# Kasli-SOC_linear.net
KiCad netlist of a schematic drawn in Altium Designer
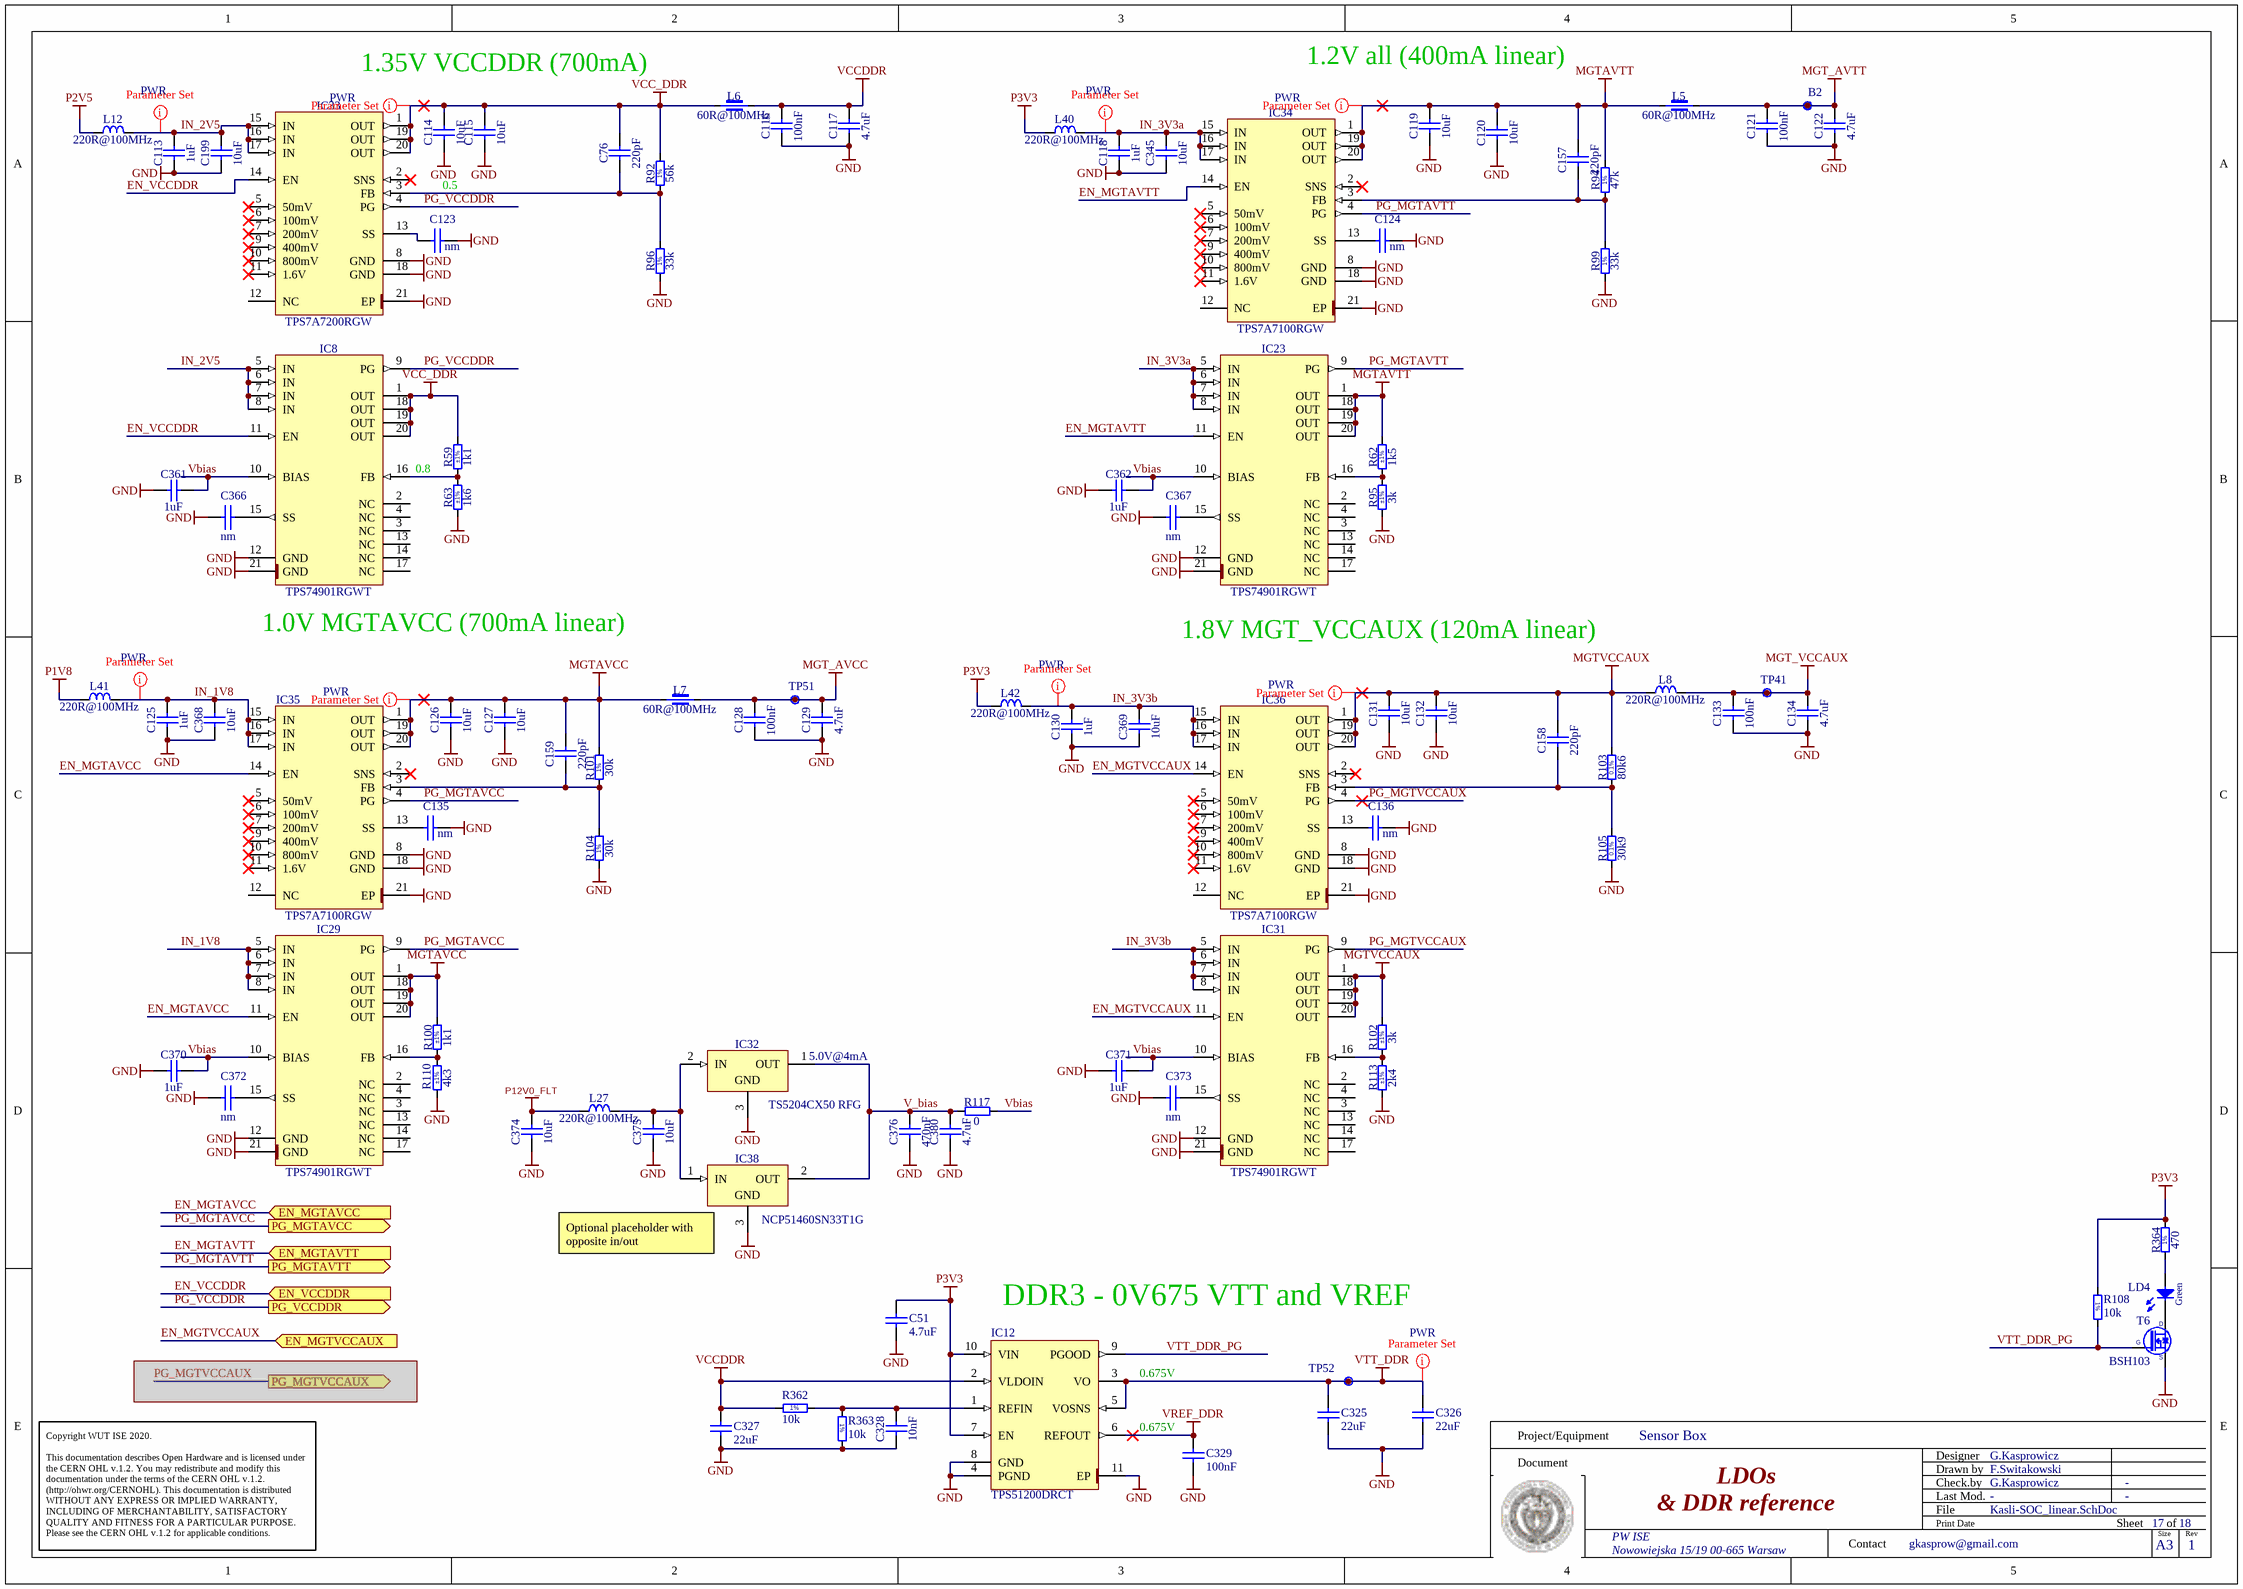
[diagram p0: Kasli-SOC_linear.SchDoc]

(export (version "E")
  (design (tool "Eeschema 10.0.6"))
  (components
    (comp (ref "B2")
      (value "SMD Pad")
      (footprint "C75")
      (description "Through Hole Pad")
      (fields (field (name "PART NUMBER") "SMD_PAD_D0.75MM") (field (name "AUTHOR") "CERN DEM BC"))
      (libsource (lib "Eletro-mechanical") (part "Single SMD Pad (Round)"))
    )
    (comp (ref "C51")
      (value "4.7uF")
      (footprint "CAPC1608X87N")
      (description "Non-polarised capacitor")
      (fields
        (field (name "PART NUMBER") "CC0603_4.7UF_6.3V_10%_X5R")
        (field (name "VOLTAGE") "6.3V")
        (field (name "AUTHOR") "CERN DEM JLC")
      )
      (libsource (lib "Capacitors") (part "Capacitor - non polarized"))
    )
    (comp (ref "C76")
      (value "220pF")
      (footprint "CAPC1005X55N")
      (description "Non-polarised capacitor")
      (fields
        (field (name "PART NUMBER") "CC0402_220PF_50V_5%_C0G")
        (field (name "VOLTAGE") "50V")
        (field (name "AUTHOR") "CERN DEM JLC")
      )
      (libsource (lib "Capacitors") (part "Capacitor - non polarized"))
    )
    (comp (ref "C113")
      (value "1uF")
      (footprint "CAPC1608X87N")
      (description "Non-polarised capacitor")
      (fields
        (field (name "PART NUMBER") "CC0603_1UF_25V_10%_X7R")
        (field (name "VOLTAGE") "25V")
        (field (name "AUTHOR") "CERN DEM JLC")
      )
      (libsource (lib "Capacitors") (part "Capacitor - non polarized"))
    )
    (comp (ref "C114")
      (value "10uF")
      (footprint "CAPC1005X70N")
      (description "Non-polarised capacitor")
      (fields
        (field (name "PART NUMBER") "CC0402_10UF_6.3V_20%_X5R")
        (field (name "VOLTAGE") "6.3V")
        (field (name "AUTHOR") "CERN DEM JLC")
      )
      (libsource (lib "Capacitors") (part "Capacitor - non polarized"))
    )
    (comp (ref "C115")
      (value "10uF")
      (footprint "CAPC1005X70N")
      (description "Non-polarised capacitor")
      (fields
        (field (name "PART NUMBER") "CC0402_10UF_6.3V_20%_X5R")
        (field (name "VOLTAGE") "6.3V")
        (field (name "AUTHOR") "CERN DEM JLC")
      )
      (libsource (lib "Capacitors") (part "Capacitor - non polarized"))
    )
    (comp (ref "C116")
      (value "100nF")
      (footprint "CAPC1005X55N")
      (description "Non-polarised capacitor")
      (fields
        (field (name "PART NUMBER") "CC0402_100NF_16V_10%_X7R")
        (field (name "VOLTAGE") "16V")
        (field (name "AUTHOR") "CERN DEM JLC")
      )
      (libsource (lib "Capacitors") (part "Capacitor - non polarized"))
    )
    (comp (ref "C117")
      (value "4.7uF")
      (footprint "CAPC1005X55N")
      (description "Non-polarised capacitor")
      (fields
        (field (name "PART NUMBER") "CC0402_4.7UF_6.3V_20%_X5R")
        (field (name "VOLTAGE") "6.3V")
        (field (name "AUTHOR") "CERN DEM JLC")
      )
      (libsource (lib "Capacitors") (part "Capacitor - non polarized"))
    )
    (comp (ref "C118")
      (value "1uF")
      (footprint "CAPC1608X87N")
      (description "Non-polarised capacitor")
      (fields
        (field (name "PART NUMBER") "CC0603_1UF_25V_10%_X7R")
        (field (name "VOLTAGE") "25V")
        (field (name "AUTHOR") "CERN DEM JLC")
      )
      (libsource (lib "Capacitors") (part "Capacitor - non polarized"))
    )
    (comp (ref "C119")
      (value "10uF")
      (footprint "CAPC1005X70N")
      (description "Non-polarised capacitor")
      (fields
        (field (name "PART NUMBER") "CC0402_10UF_6.3V_20%_X5R")
        (field (name "VOLTAGE") "6.3V")
        (field (name "AUTHOR") "CERN DEM JLC")
      )
      (libsource (lib "Capacitors") (part "Capacitor - non polarized"))
    )
    (comp (ref "C120")
      (value "10uF")
      (footprint "CAPC1005X70N")
      (description "Non-polarised capacitor")
      (fields
        (field (name "PART NUMBER") "CC0402_10UF_6.3V_20%_X5R")
        (field (name "VOLTAGE") "6.3V")
        (field (name "AUTHOR") "CERN DEM JLC")
      )
      (libsource (lib "Capacitors") (part "Capacitor - non polarized"))
    )
    (comp (ref "C121")
      (value "100nF")
      (footprint "CAPC1005X55N")
      (description "Non-polarised capacitor")
      (fields
        (field (name "PART NUMBER") "CC0402_100NF_16V_10%_X7R")
        (field (name "VOLTAGE") "16V")
        (field (name "AUTHOR") "CERN DEM JLC")
      )
      (libsource (lib "Capacitors") (part "Capacitor - non polarized"))
    )
    (comp (ref "C122")
      (value "4.7uF")
      (footprint "CAPC1005X55N")
      (description "Non-polarised capacitor")
      (fields
        (field (name "PART NUMBER") "CC0402_4.7UF_6.3V_20%_X5R")
        (field (name "VOLTAGE") "6.3V")
        (field (name "AUTHOR") "CERN DEM JLC")
      )
      (libsource (lib "Capacitors") (part "Capacitor - non polarized"))
    )
    (comp (ref "C123")
      (value "nm")
      (footprint "0402C")
      (description "Capacitor SMD")
      (libsource (lib "LIBRARY_SCH") (part "CAP_SMD_0402"))
    )
    (comp (ref "C124")
      (value "nm")
      (footprint "0402C")
      (description "Capacitor SMD")
      (libsource (lib "LIBRARY_SCH") (part "CAP_SMD_0402"))
    )
    (comp (ref "C125")
      (value "1uF")
      (footprint "CAPC1608X87N")
      (description "Non-polarised capacitor")
      (fields
        (field (name "PART NUMBER") "CC0603_1UF_25V_10%_X7R")
        (field (name "VOLTAGE") "25V")
        (field (name "AUTHOR") "CERN DEM JLC")
      )
      (libsource (lib "Capacitors") (part "Capacitor - non polarized"))
    )
    (comp (ref "C126")
      (value "10uF")
      (footprint "CAPC1005X70N")
      (description "Non-polarised capacitor")
      (fields
        (field (name "PART NUMBER") "CC0402_10UF_6.3V_20%_X5R")
        (field (name "VOLTAGE") "6.3V")
        (field (name "AUTHOR") "CERN DEM JLC")
      )
      (libsource (lib "Capacitors") (part "Capacitor - non polarized"))
    )
    (comp (ref "C127")
      (value "10uF")
      (footprint "CAPC1005X70N")
      (description "Non-polarised capacitor")
      (fields
        (field (name "PART NUMBER") "CC0402_10UF_6.3V_20%_X5R")
        (field (name "VOLTAGE") "6.3V")
        (field (name "AUTHOR") "CERN DEM JLC")
      )
      (libsource (lib "Capacitors") (part "Capacitor - non polarized"))
    )
    (comp (ref "C128")
      (value "100nF")
      (footprint "CAPC1005X55N")
      (description "Non-polarised capacitor")
      (fields
        (field (name "PART NUMBER") "CC0402_100NF_16V_10%_X7R")
        (field (name "VOLTAGE") "16V")
        (field (name "AUTHOR") "CERN DEM JLC")
      )
      (libsource (lib "Capacitors") (part "Capacitor - non polarized"))
    )
    (comp (ref "C129")
      (value "4.7uF")
      (footprint "CAPC1005X55N")
      (description "Non-polarised capacitor")
      (fields
        (field (name "PART NUMBER") "CC0402_4.7UF_6.3V_20%_X5R")
        (field (name "VOLTAGE") "6.3V")
        (field (name "AUTHOR") "CERN DEM JLC")
      )
      (libsource (lib "Capacitors") (part "Capacitor - non polarized"))
    )
    (comp (ref "C130")
      (value "1uF")
      (footprint "CAPC1608X87N")
      (description "Non-polarised capacitor")
      (fields
        (field (name "PART NUMBER") "CC0603_1UF_25V_10%_X7R")
        (field (name "VOLTAGE") "25V")
        (field (name "AUTHOR") "CERN DEM JLC")
      )
      (libsource (lib "Capacitors") (part "Capacitor - non polarized"))
    )
    (comp (ref "C131")
      (value "10uF")
      (footprint "CAPC1005X70N")
      (description "Non-polarised capacitor")
      (fields
        (field (name "PART NUMBER") "CC0402_10UF_6.3V_20%_X5R")
        (field (name "VOLTAGE") "6.3V")
        (field (name "AUTHOR") "CERN DEM JLC")
      )
      (libsource (lib "Capacitors") (part "Capacitor - non polarized"))
    )
    (comp (ref "C132")
      (value "10uF")
      (footprint "CAPC1005X70N")
      (description "Non-polarised capacitor")
      (fields
        (field (name "PART NUMBER") "CC0402_10UF_6.3V_20%_X5R")
        (field (name "VOLTAGE") "6.3V")
        (field (name "AUTHOR") "CERN DEM JLC")
      )
      (libsource (lib "Capacitors") (part "Capacitor - non polarized"))
    )
    (comp (ref "C133")
      (value "100nF")
      (footprint "CAPC1005X55N")
      (description "Non-polarised capacitor")
      (fields
        (field (name "PART NUMBER") "CC0402_100NF_16V_10%_X7R")
        (field (name "VOLTAGE") "16V")
        (field (name "AUTHOR") "CERN DEM JLC")
      )
      (libsource (lib "Capacitors") (part "Capacitor - non polarized"))
    )
    (comp (ref "C134")
      (value "4.7uF")
      (footprint "CAPC1005X55N")
      (description "Non-polarised capacitor")
      (fields
        (field (name "PART NUMBER") "CC0402_4.7UF_6.3V_20%_X5R")
        (field (name "VOLTAGE") "6.3V")
        (field (name "AUTHOR") "CERN DEM JLC")
      )
      (libsource (lib "Capacitors") (part "Capacitor - non polarized"))
    )
    (comp (ref "C135")
      (value "nm")
      (footprint "0402C")
      (description "Capacitor SMD")
      (libsource (lib "LIBRARY_SCH") (part "CAP_SMD_0402"))
    )
    (comp (ref "C136")
      (value "nm")
      (footprint "0402C")
      (description "Capacitor SMD")
      (libsource (lib "LIBRARY_SCH") (part "CAP_SMD_0402"))
    )
    (comp (ref "C157")
      (value "220pF")
      (footprint "CAPC1005X55N")
      (description "Non-polarised capacitor")
      (fields
        (field (name "PART NUMBER") "CC0402_220PF_50V_5%_C0G")
        (field (name "VOLTAGE") "50V")
        (field (name "AUTHOR") "CERN DEM JLC")
      )
      (libsource (lib "Capacitors") (part "Capacitor - non polarized"))
    )
    (comp (ref "C158")
      (value "220pF")
      (footprint "CAPC1005X55N")
      (description "Non-polarised capacitor")
      (fields
        (field (name "PART NUMBER") "CC0402_220PF_50V_5%_C0G")
        (field (name "VOLTAGE") "50V")
        (field (name "AUTHOR") "CERN DEM JLC")
      )
      (libsource (lib "Capacitors") (part "Capacitor - non polarized"))
    )
    (comp (ref "C159")
      (value "220pF")
      (footprint "CAPC1005X55N")
      (description "Non-polarised capacitor")
      (fields
        (field (name "PART NUMBER") "CC0402_220PF_50V_5%_C0G")
        (field (name "VOLTAGE") "50V")
        (field (name "AUTHOR") "CERN DEM JLC")
      )
      (libsource (lib "Capacitors") (part "Capacitor - non polarized"))
    )
    (comp (ref "C199")
      (value "10uF")
      (footprint "CAPC1005X70N")
      (description "Non-polarised capacitor")
      (fields
        (field (name "PART NUMBER") "CC0402_10UF_6.3V_20%_X5R")
        (field (name "VOLTAGE") "6.3V")
        (field (name "AUTHOR") "CERN DEM JLC")
      )
      (libsource (lib "Capacitors") (part "Capacitor - non polarized"))
    )
    (comp (ref "C325")
      (value "22uF")
      (footprint "CAPC3216X180N")
      (description "Non-polarised capacitor")
      (fields
        (field (name "PART NUMBER") "CC1206_22UF_10V_10%_X7R")
        (field (name "VOLTAGE") "10V")
        (field (name "AUTHOR") "CERN DEM JLC")
      )
      (libsource (lib "Capacitors") (part "Capacitor - non polarized"))
    )
    (comp (ref "C326")
      (value "22uF")
      (footprint "CAPC3216X180N")
      (description "Non-polarised capacitor")
      (fields
        (field (name "PART NUMBER") "CC1206_22UF_10V_10%_X7R")
        (field (name "VOLTAGE") "10V")
        (field (name "AUTHOR") "CERN DEM JLC")
      )
      (libsource (lib "Capacitors") (part "Capacitor - non polarized"))
    )
    (comp (ref "C327")
      (value "22uF")
      (footprint "CAPC3216X180N")
      (description "Non-polarised capacitor")
      (fields
        (field (name "PART NUMBER") "CC1206_22UF_10V_10%_X7R")
        (field (name "VOLTAGE") "10V")
        (field (name "AUTHOR") "CERN DEM JLC")
      )
      (libsource (lib "Capacitors") (part "Capacitor - non polarized"))
    )
    (comp (ref "C328")
      (value "10nF")
      (footprint "CAPC1005X55N")
      (description "Non-polarised capacitor")
      (fields
        (field (name "PART NUMBER") "CC0402_10NF_16V_10%_X7R")
        (field (name "VOLTAGE") "16V")
        (field (name "AUTHOR") "CERN DEM JLC")
      )
      (libsource (lib "Capacitors") (part "Capacitor - non polarized"))
    )
    (comp (ref "C329")
      (value "100nF")
      (footprint "CAPC1005X55N")
      (description "Non-polarised capacitor")
      (fields
        (field (name "PART NUMBER") "CC0402_100NF_16V_10%_X7R")
        (field (name "VOLTAGE") "16V")
        (field (name "AUTHOR") "CERN DEM JLC")
      )
      (libsource (lib "Capacitors") (part "Capacitor - non polarized"))
    )
    (comp (ref "C345")
      (value "10uF")
      (footprint "CAPC1005X70N")
      (description "Non-polarised capacitor")
      (fields
        (field (name "PART NUMBER") "CC0402_10UF_6.3V_20%_X5R")
        (field (name "VOLTAGE") "6.3V")
        (field (name "AUTHOR") "CERN DEM JLC")
      )
      (libsource (lib "Capacitors") (part "Capacitor - non polarized"))
    )
    (comp (ref "C361")
      (value "1uF")
      (footprint "CAPC1005X55N")
      (description "Non-polarised capacitor")
      (fields
        (field (name "PART NUMBER") "CC0402_1UF_16V_10%_X5R")
        (field (name "VOLTAGE") "16V")
        (field (name "AUTHOR") "CERN DEM JLC")
      )
      (libsource (lib "Capacitors") (part "Capacitor - non polarized"))
    )
    (comp (ref "C362")
      (value "1uF")
      (footprint "CAPC1005X55N")
      (description "Non-polarised capacitor")
      (fields
        (field (name "PART NUMBER") "CC0402_1UF_16V_10%_X5R")
        (field (name "VOLTAGE") "16V")
        (field (name "AUTHOR") "CERN DEM JLC")
      )
      (libsource (lib "Capacitors") (part "Capacitor - non polarized"))
    )
    (comp (ref "C366")
      (value "nm")
      (footprint "0402C")
      (description "Capacitor SMD")
      (libsource (lib "LIBRARY_SCH") (part "CAP_SMD_0402"))
    )
    (comp (ref "C367")
      (value "nm")
      (footprint "0402C")
      (description "Capacitor SMD")
      (libsource (lib "LIBRARY_SCH") (part "CAP_SMD_0402"))
    )
    (comp (ref "C368")
      (value "10uF")
      (footprint "CAPC1005X70N")
      (description "Non-polarised capacitor")
      (fields
        (field (name "PART NUMBER") "CC0402_10UF_6.3V_20%_X5R")
        (field (name "VOLTAGE") "6.3V")
        (field (name "AUTHOR") "CERN DEM JLC")
      )
      (libsource (lib "Capacitors") (part "Capacitor - non polarized"))
    )
    (comp (ref "C369")
      (value "10uF")
      (footprint "CAPC1005X70N")
      (description "Non-polarised capacitor")
      (fields
        (field (name "PART NUMBER") "CC0402_10UF_6.3V_20%_X5R")
        (field (name "VOLTAGE") "6.3V")
        (field (name "AUTHOR") "CERN DEM JLC")
      )
      (libsource (lib "Capacitors") (part "Capacitor - non polarized"))
    )
    (comp (ref "C370")
      (value "1uF")
      (footprint "CAPC1005X55N")
      (description "Non-polarised capacitor")
      (fields
        (field (name "PART NUMBER") "CC0402_1UF_16V_10%_X5R")
        (field (name "VOLTAGE") "16V")
        (field (name "AUTHOR") "CERN DEM JLC")
      )
      (libsource (lib "Capacitors") (part "Capacitor - non polarized"))
    )
    (comp (ref "C371")
      (value "1uF")
      (footprint "CAPC1005X55N")
      (description "Non-polarised capacitor")
      (fields
        (field (name "PART NUMBER") "CC0402_1UF_16V_10%_X5R")
        (field (name "VOLTAGE") "16V")
        (field (name "AUTHOR") "CERN DEM JLC")
      )
      (libsource (lib "Capacitors") (part "Capacitor - non polarized"))
    )
    (comp (ref "C372")
      (value "nm")
      (footprint "0402C")
      (description "Capacitor SMD")
      (libsource (lib "LIBRARY_SCH") (part "CAP_SMD_0402"))
    )
    (comp (ref "C373")
      (value "nm")
      (footprint "0402C")
      (description "Capacitor SMD")
      (libsource (lib "LIBRARY_SCH") (part "CAP_SMD_0402"))
    )
    (comp (ref "C374")
      (value "10uF")
      (footprint "CAPC2012X95N")
      (description "Non-polarised capacitor")
      (fields
        (field (name "PART NUMBER") "CC0805_10UF_25V_10%_X5R")
        (field (name "VOLTAGE") "25V")
        (field (name "AUTHOR") "CERN DEM JLC")
      )
      (libsource (lib "Capacitors") (part "Capacitor - non polarized"))
    )
    (comp (ref "C375")
      (value "10uF")
      (footprint "CAPC2012X95N")
      (description "Non-polarised capacitor")
      (fields
        (field (name "PART NUMBER") "CC0805_10UF_25V_10%_X5R")
        (field (name "VOLTAGE") "25V")
        (field (name "AUTHOR") "CERN DEM JLC")
      )
      (libsource (lib "Capacitors") (part "Capacitor - non polarized"))
    )
    (comp (ref "C376")
      (value "470nF")
      (footprint "CAPC1608X87N")
      (description "Non-polarised capacitor")
      (fields
        (field (name "PART NUMBER") "CC0603_470NF_16V_10%_X5R")
        (field (name "VOLTAGE") "16V")
        (field (name "AUTHOR") "CERN DEM JLC")
      )
      (libsource (lib "Capacitors") (part "Capacitor - non polarized"))
    )
    (comp (ref "C380")
      (value "4.7uF")
      (footprint "CAPC1005X55N")
      (description "Non-polarised capacitor")
      (fields
        (field (name "PART NUMBER") "CC0402_4.7UF_6.3V_20%_X5R")
        (field (name "VOLTAGE") "6.3V")
        (field (name "AUTHOR") "CERN DEM JLC")
      )
      (libsource (lib "Capacitors") (part "Capacitor - non polarized"))
    )
    (comp (ref "IC8")
      (value "TPS74901RGWT")
      (footprint "QFN65P500X500X100-21N-S325")
      (description "3A, 0.8 to 3.6V Adjustable Low-Dropout Linear Regulator with Programmable Soft-Start")
      (fields
        (field (name "MANUFACTURER") "TEXAS INSTRUMENTS")
        (field (name "MANUFACTURER PART NUMBER") "TPS74901RGW")
        (field (name "AUTHOR") "CERN DEM JLC")
      )
      (libsource (lib "ICs And Semiconductors") (part "TPS74901RGWT"))
    )
    (comp (ref "IC12")
      (value "TPS51200DRCT")
      (footprint "TEXAS_DRC (S-PVSON-N10)")
      (description "Sink/Source DDR Termination Regulator")
      (fields (field (name "MANUFACTURER") "TEXAS INSTRUMENTS") (field (name "AUTHOR") "CERN DEM JLC"))
      (libsource (lib "ICs And Semiconductors") (part "TPS51200DRC"))
    )
    (comp (ref "IC23")
      (value "TPS74901RGWT")
      (footprint "QFN65P500X500X100-21N-S325")
      (description "3A, 0.8 to 3.6V Adjustable Low-Dropout Linear Regulator with Programmable Soft-Start")
      (fields
        (field (name "MANUFACTURER") "TEXAS INSTRUMENTS")
        (field (name "MANUFACTURER PART NUMBER") "TPS74901RGW")
        (field (name "AUTHOR") "CERN DEM JLC")
      )
      (libsource (lib "ICs And Semiconductors") (part "TPS74901RGWT"))
    )
    (comp (ref "IC29")
      (value "TPS74901RGWT")
      (footprint "QFN65P500X500X100-21N-S325")
      (description "3A, 0.8 to 3.6V Adjustable Low-Dropout Linear Regulator with Programmable Soft-Start")
      (fields
        (field (name "MANUFACTURER") "TEXAS INSTRUMENTS")
        (field (name "MANUFACTURER PART NUMBER") "TPS74901RGW")
        (field (name "AUTHOR") "CERN DEM JLC")
      )
      (libsource (lib "ICs And Semiconductors") (part "TPS74901RGWT"))
    )
    (comp (ref "IC31")
      (value "TPS74901RGWT")
      (footprint "QFN65P500X500X100-21N-S325")
      (description "3A, 0.8 to 3.6V Adjustable Low-Dropout Linear Regulator with Programmable Soft-Start")
      (fields
        (field (name "MANUFACTURER") "TEXAS INSTRUMENTS")
        (field (name "MANUFACTURER PART NUMBER") "TPS74901RGW")
        (field (name "AUTHOR") "CERN DEM JLC")
      )
      (libsource (lib "ICs And Semiconductors") (part "TPS74901RGWT"))
    )
    (comp (ref "IC32")
      (value "TS5204CX50 RFG")
      (footprint "SOT95P280X115-3N")
      (description "3-Terminal Regulator 1=OUT 2=IN 3=GND")
      (fields (field (name "MANUFACTURER") "TAIWAN SEMICONDUCTOR") (field (name "AUTHOR") "CERN DEM JLC"))
      (libsource (lib "ICs And Semiconductors") (part "REG3 1OUT-2IN-3GND"))
    )
    (comp (ref "IC33")
      (value "TPS7A7200RGW")
      (footprint "QFN65P500X500X100-21N-S325")
      (description "2-A, Fast-Transient, Low-Dropout Voltage Regulator")
      (fields (field (name "MANUFACTURER") "TEXAS INSTRUMENTS") (field (name "AUTHOR") "CERN DEM MR"))
      (libsource (lib "ICs And Semiconductors") (part "TPS7A7200RGW"))
    )
    (comp (ref "IC34")
      (value "TPS7A7100RGW")
      (footprint "QFN65P500X500X100-21N-S325")
      (description "1-A, Fast-Transient, Low-Dropout Voltage Regulator")
      (fields (field (name "MANUFACTURER") "TEXAS INSTRUMENTS") (field (name "AUTHOR") "CERN DEM MR"))
      (libsource (lib "ICs And Semiconductors") (part "TPS7A7100RGW"))
    )
    (comp (ref "IC35")
      (value "TPS7A7100RGW")
      (footprint "QFN65P500X500X100-21N-S325")
      (description "1-A, Fast-Transient, Low-Dropout Voltage Regulator")
      (fields (field (name "MANUFACTURER") "TEXAS INSTRUMENTS") (field (name "AUTHOR") "CERN DEM MR"))
      (libsource (lib "ICs And Semiconductors") (part "TPS7A7100RGW"))
    )
    (comp (ref "IC36")
      (value "TPS7A7100RGW")
      (footprint "QFN65P500X500X100-21N-S325")
      (description "1-A, Fast-Transient, Low-Dropout Voltage Regulator")
      (fields (field (name "MANUFACTURER") "TEXAS INSTRUMENTS") (field (name "AUTHOR") "CERN DEM MR"))
      (libsource (lib "ICs And Semiconductors") (part "TPS7A7100RGW"))
    )
    (comp (ref "IC38")
      (value "NCP51460SN33T1G")
      (footprint "SOT95P240X110-3N")
      (description "3-Terminal Regulator 1=IN 2=OUT 3=GND")
      (fields
        (field (name "PART NUMBER") "NCP51460SN50T1G")
        (field (name "MANUFACTURER") "ON SEMICONDUCTOR")
        (field (name "AUTHOR") "CERN DEM MR")
      )
      (libsource (lib "ICs And Semiconductors") (part "REG3 1IN-2OUT-3GND"))
    )
    (comp (ref "L5")
      (value "60R@100MHz")
      (footprint "INDC4516X180N")
      (fields
        (field (name "MANUFACTURER PART NUMBER") "BLM41PG600SN1L")
        (field (name "MANUFACTURER") "MURATA")
        (field (name "PART NUMBER") "IND1806_MURATA_BLM41PG600SN1L")
        (field (name "AUTHOR") "CERN DEM JLC")
      )
      (libsource (lib "Inductors & Transformers") (part "Ferrite Bead"))
    )
    (comp (ref "L6")
      (value "60R@100MHz")
      (footprint "INDC4516X180N")
      (fields
        (field (name "MANUFACTURER PART NUMBER") "BLM41PG600SN1L")
        (field (name "MANUFACTURER") "MURATA")
        (field (name "PART NUMBER") "IND1806_MURATA_BLM41PG600SN1L")
        (field (name "AUTHOR") "CERN DEM JLC")
      )
      (libsource (lib "Inductors & Transformers") (part "Ferrite Bead"))
    )
    (comp (ref "L7")
      (value "60R@100MHz")
      (footprint "INDC4516X180N")
      (fields
        (field (name "MANUFACTURER PART NUMBER") "BLM41PG600SN1L")
        (field (name "MANUFACTURER") "MURATA")
        (field (name "PART NUMBER") "IND1806_MURATA_BLM41PG600SN1L")
        (field (name "AUTHOR") "CERN DEM JLC")
      )
      (libsource (lib "Inductors & Transformers") (part "Ferrite Bead"))
    )
    (comp (ref "L8")
      (value "220R@100MHz")
      (footprint "INDC2012X105N")
      (description "Inductor")
      (fields
        (field (name "PART NUMBER") "IND0805_MURATA_BLM21PG221SN1D")
        (field (name "POWER") "2A")
        (field (name "AUTHOR") "CERN DEM JLC")
      )
      (libsource (lib "Inductors & Transformers") (part "Inductor"))
    )
    (comp (ref "L12")
      (value "220R@100MHz")
      (footprint "INDC2012X105N")
      (description "Inductor")
      (fields
        (field (name "PART NUMBER") "IND0805_MURATA_BLM21PG221SN1D")
        (field (name "POWER") "2A")
        (field (name "AUTHOR") "CERN DEM JLC")
      )
      (libsource (lib "Inductors & Transformers") (part "Inductor"))
    )
    (comp (ref "L27")
      (value "220R@100MHz")
      (footprint "INDC2012X105N")
      (description "Inductor")
      (fields
        (field (name "PART NUMBER") "IND0805_MURATA_BLM21PG221SN1D")
        (field (name "POWER") "2A")
        (field (name "AUTHOR") "CERN DEM JLC")
      )
      (libsource (lib "Inductors & Transformers") (part "Inductor"))
    )
    (comp (ref "L40")
      (value "220R@100MHz")
      (footprint "INDC2012X105N")
      (description "Inductor")
      (fields
        (field (name "PART NUMBER") "IND0805_MURATA_BLM21PG221SN1D")
        (field (name "POWER") "2A")
        (field (name "AUTHOR") "CERN DEM JLC")
      )
      (libsource (lib "Inductors & Transformers") (part "Inductor"))
    )
    (comp (ref "L41")
      (value "220R@100MHz")
      (footprint "INDC2012X105N")
      (description "Inductor")
      (fields
        (field (name "PART NUMBER") "IND0805_MURATA_BLM21PG221SN1D")
        (field (name "POWER") "2A")
        (field (name "AUTHOR") "CERN DEM JLC")
      )
      (libsource (lib "Inductors & Transformers") (part "Inductor"))
    )
    (comp (ref "L42")
      (value "220R@100MHz")
      (footprint "INDC2012X105N")
      (description "Inductor")
      (fields
        (field (name "PART NUMBER") "IND0805_MURATA_BLM21PG221SN1D")
        (field (name "POWER") "2A")
        (field (name "AUTHOR") "CERN DEM JLC")
      )
      (libsource (lib "Inductors & Transformers") (part "Inductor"))
    )
    (comp (ref "LD4")
      (value "Green")
      (footprint "LED_KINGBRIGHT_KPH-1608CGCK")
      (description "LED Green 1C 2A")
      (fields
        (field (name "MANUFACTURER PART NUMBER") "KPH-1608CGCK")
        (field (name "PART NUMBER") "LED_KINGBRIGHT_KPH-1608CGCK")
        (field (name "AUTHOR") "CERN DEM JLC")
      )
      (libsource (lib "ICs And Semiconductors") (part "LED Green 1C 2A"))
    )
    (comp (ref "R59")
      (value "1k1")
      (footprint "RESC1005X40N")
      (description "Resistor - 1%")
      (fields
        (field (name "TOLERANCE") "±1%")
        (field (name "PART NUMBER") "R0402_1K1_1%_0.0625W_100PPM")
        (field (name "POWER") "0.0625W")
        (field (name "AUTHOR") "CERN DEM JLC")
      )
      (libsource (lib "Resistors") (part "Resistor - 1%"))
    )
    (comp (ref "R62")
      (value "1k5")
      (footprint "RESC1005X40N")
      (description "Resistor - 1%")
      (fields
        (field (name "TOLERANCE") "±1%")
        (field (name "PART NUMBER") "R0402_1K5_1%_0.0625W_100PPM")
        (field (name "POWER") "0.0625W")
        (field (name "AUTHOR") "CERN DEM JLC")
      )
      (libsource (lib "Resistors") (part "Resistor - 1%"))
    )
    (comp (ref "R63")
      (value "1k6")
      (footprint "RESC1005X40N")
      (description "Resistor - 1%")
      (fields
        (field (name "TOLERANCE") "±1%")
        (field (name "PART NUMBER") "R0402_1K6_1%_0.0625W_100PPM")
        (field (name "POWER") "0.0625W")
        (field (name "AUTHOR") "CERN DEM JLC")
      )
      (libsource (lib "Resistors") (part "Resistor - 1%"))
    )
    (comp (ref "R92")
      (value "56k")
      (footprint "RESC1005X40N")
      (description "Resistor - 1%")
      (fields
        (field (name "PART NUMBER") "R0402_56K_1%_0.0625W_100PPM")
        (field (name "POWER") "0.0625W")
        (field (name "AUTHOR") "CERN DEM JLC")
      )
      (libsource (lib "Resistors") (part "Resistor - 1%"))
    )
    (comp (ref "R94")
      (value "47k")
      (footprint "RESC1005X40N")
      (description "Resistor - 1%")
      (fields
        (field (name "PART NUMBER") "R0402_47K_1%_0.0625W_100PPM")
        (field (name "POWER") "0.0625W")
        (field (name "AUTHOR") "CERN DEM JLC")
      )
      (libsource (lib "Resistors") (part "Resistor - 1%"))
    )
    (comp (ref "R95")
      (value "3k")
      (footprint "RESC1005X40N")
      (description "Resistor - 1%")
      (fields
        (field (name "TOLERANCE") "±1%")
        (field (name "PART NUMBER") "R0402_3K_1%_0.0625W_100PPM")
        (field (name "POWER") "0.0625W")
        (field (name "AUTHOR") "CERN DEM JLC")
      )
      (libsource (lib "Resistors") (part "Resistor - 1%"))
    )
    (comp (ref "R96")
      (value "33k")
      (footprint "RESC1005X40N")
      (description "Resistor - 1%")
      (fields
        (field (name "PART NUMBER") "R0402_33K_1%_0.0625W_100PPM")
        (field (name "POWER") "0.0625W")
        (field (name "AUTHOR") "CERN DEM JLC")
      )
      (libsource (lib "Resistors") (part "Resistor - 1%"))
    )
    (comp (ref "R99")
      (value "33k")
      (footprint "RESC1005X40N")
      (description "Resistor - 1%")
      (fields
        (field (name "PART NUMBER") "R0402_33K_1%_0.0625W_100PPM")
        (field (name "POWER") "0.0625W")
        (field (name "AUTHOR") "CERN DEM JLC")
      )
      (libsource (lib "Resistors") (part "Resistor - 1%"))
    )
    (comp (ref "R100")
      (value "1k1")
      (footprint "RESC1005X40N")
      (description "Resistor - 1%")
      (fields
        (field (name "TOLERANCE") "±1%")
        (field (name "PART NUMBER") "R0402_1K1_1%_0.0625W_100PPM")
        (field (name "POWER") "0.0625W")
        (field (name "AUTHOR") "CERN DEM JLC")
      )
      (libsource (lib "Resistors") (part "Resistor - 1%"))
    )
    (comp (ref "R101")
      (value "30k")
      (footprint "RESC1005X40N")
      (description "Resistor - 1%")
      (fields
        (field (name "PART NUMBER") "R0402_30K_1%_0.0625W_100PPM")
        (field (name "POWER") "0.0625W")
        (field (name "AUTHOR") "CERN DEM JLC")
      )
      (libsource (lib "Resistors") (part "Resistor - 1%"))
    )
    (comp (ref "R102")
      (value "3k")
      (footprint "RESC1005X40N")
      (description "Resistor - 1%")
      (fields
        (field (name "TOLERANCE") "±1%")
        (field (name "PART NUMBER") "R0402_3K_1%_0.0625W_100PPM")
        (field (name "POWER") "0.0625W")
        (field (name "AUTHOR") "CERN DEM JLC")
      )
      (libsource (lib "Resistors") (part "Resistor - 1%"))
    )
    (comp (ref "R103")
      (value "80k6")
      (footprint "RESC1608X55N")
      (description "Resistor - 0.1%")
      (fields
        (field (name "PART NUMBER") "R0603_80K6_0.1%_0.063W_10PPM")
        (field (name "POWER") "0.063W")
        (field (name "AUTHOR") "CERN DEM JLC")
      )
      (libsource (lib "Resistors") (part "Resistor - 0.1%"))
    )
    (comp (ref "R104")
      (value "30k")
      (footprint "RESC1005X40N")
      (description "Resistor - 1%")
      (fields
        (field (name "PART NUMBER") "R0402_30K_1%_0.0625W_100PPM")
        (field (name "POWER") "0.0625W")
        (field (name "AUTHOR") "CERN DEM JLC")
      )
      (libsource (lib "Resistors") (part "Resistor - 1%"))
    )
    (comp (ref "R105")
      (value "30k9")
      (footprint "RESC1608X55N")
      (description "Resistor - 0.1%")
      (fields
        (field (name "PART NUMBER") "R0603_30K9_0.1%_0.063W_10PPM")
        (field (name "POWER") "0.063W")
        (field (name "AUTHOR") "CERN DEM JLC")
      )
      (libsource (lib "Resistors") (part "Resistor - 0.1%"))
    )
    (comp (ref "R108")
      (value "10k")
      (footprint "RESC1005X40N")
      (description "Resistor - 1%")
      (fields
        (field (name "PART NUMBER") "R0402_10K_1%_0.0625W_100PPM")
        (field (name "POWER") "0.0625W")
        (field (name "AUTHOR") "CERN DEM JLC")
      )
      (libsource (lib "Resistors") (part "Resistor - 1%"))
    )
    (comp (ref "R110")
      (value "4k3")
      (footprint "RESC1005X40N")
      (description "Resistor - 1%")
      (fields
        (field (name "TOLERANCE") "±1%")
        (field (name "PART NUMBER") "R0402_4K3_1%_0.0625W_100PPM")
        (field (name "POWER") "0.0625W")
        (field (name "AUTHOR") "CERN DEM JLC")
      )
      (libsource (lib "Resistors") (part "Resistor - 1%"))
    )
    (comp (ref "R113")
      (value "2k4")
      (footprint "RESC1005X40N")
      (description "Resistor - 1%")
      (fields
        (field (name "TOLERANCE") "±1%")
        (field (name "PART NUMBER") "R0402_2K4_1%_0.0625W_100PPM")
        (field (name "POWER") "0.0625W")
        (field (name "AUTHOR") "CERN DEM JLC")
      )
      (libsource (lib "Resistors") (part "Resistor - 1%"))
    )
    (comp (ref "R117")
      (value "0")
      (footprint "RESC1005X40N")
      (description "Resistor")
      (fields
        (field (name "PART NUMBER") "R0402_0R_JUMPER")
        (field (name "MANUFACTURER") "GENERIC")
        (field (name "AUTHOR") "CERN DEM JLC")
      )
      (libsource (lib "Resistors") (part "Resistor"))
    )
    (comp (ref "R362")
      (value "10k")
      (footprint "RESC1005X40N")
      (description "Resistor - 1%")
      (fields
        (field (name "PART NUMBER") "R0402_10K_1%_0.0625W_100PPM")
        (field (name "POWER") "0.0625W")
        (field (name "AUTHOR") "CERN DEM JLC")
      )
      (libsource (lib "Resistors") (part "Resistor - 1%"))
    )
    (comp (ref "R363")
      (value "10k")
      (footprint "RESC1005X40N")
      (description "Resistor - 1%")
      (fields
        (field (name "PART NUMBER") "R0402_10K_1%_0.0625W_100PPM")
        (field (name "POWER") "0.0625W")
        (field (name "AUTHOR") "CERN DEM JLC")
      )
      (libsource (lib "Resistors") (part "Resistor - 1%"))
    )
    (comp (ref "R364")
      (value "470")
      (footprint "RESC1005X40N")
      (description "Resistor - 1%")
      (fields
        (field (name "PART NUMBER") "R0402_470R_1%_0.0625W_100PPM")
        (field (name "POWER") "0.0625W")
        (field (name "AUTHOR") "CERN DEM JLC")
      )
      (libsource (lib "Resistors") (part "Resistor - 1%"))
    )
    (comp (ref "T6")
      (value "BSH103")
      (footprint "SOT95P230X110-3N")
      (description "N-CHANNEL MOSFET WITH DIODE")
      (fields (field (name "MANUFACTURER") "NEXPERIA") (field (name "AUTHOR") "CERN DEM JLC"))
      (libsource (lib "ICs And Semiconductors") (part "N-MOSFET-D 1G 2S 3D"))
    )
    (comp (ref "TP41")
      (value "Test Point")
      (footprint "TPS127")
      (fields (field (name "PART NUMBER") "SMD_PAD_1.27X1.27MM") (field (name "AUTHOR") "CERN DEM JLC"))
      (libsource (lib "Eletro-mechanical") (part "Test Point"))
    )
    (comp (ref "TP51")
      (value "Test Point")
      (footprint "TPS127")
      (fields (field (name "PART NUMBER") "SMD_PAD_1.27X1.27MM") (field (name "AUTHOR") "CERN DEM JLC"))
      (libsource (lib "Eletro-mechanical") (part "Test Point"))
    )
    (comp (ref "TP52")
      (value "Test Point")
      (footprint "TPS127")
      (fields (field (name "PART NUMBER") "SMD_PAD_1.27X1.27MM") (field (name "AUTHOR") "CERN DEM JLC"))
      (libsource (lib "Eletro-mechanical") (part "Test Point"))
    )
  )
  (nets
    (net (code "1") (name "/EN_MGTAVCC") (class "Default")
      (node (ref "IC29") (pin "11") (pinfunction "EN_11") (pintype "input"))
      (node (ref "IC35") (pin "14") (pinfunction "EN_14") (pintype "input"))
    )
    (net (code "2") (name "/EN_MGTAVTT") (class "Default")
      (node (ref "IC23") (pin "11") (pinfunction "EN_11") (pintype "input"))
      (node (ref "IC34") (pin "14") (pinfunction "EN_14") (pintype "input"))
    )
    (net (code "3") (name "/EN_MGTVCCAUX") (class "Default")
      (node (ref "IC31") (pin "11") (pinfunction "EN_11") (pintype "input"))
      (node (ref "IC36") (pin "14") (pinfunction "EN_14") (pintype "input"))
    )
    (net (code "4") (name "/EN_VCCDDR") (class "Default")
      (node (ref "IC33") (pin "14") (pinfunction "EN_14") (pintype "input"))
      (node (ref "IC8") (pin "11") (pinfunction "EN_11") (pintype "input"))
    )
    (net (code "5") (name "/IN_1V8") (class "Default")
      (node (ref "C125") (pin "2") (pinfunction "2_2") (pintype "passive"))
      (node (ref "C368") (pin "2") (pinfunction "2_2") (pintype "passive"))
      (node (ref "IC29") (pin "5") (pinfunction "IN_5") (pintype "input"))
      (node (ref "IC29") (pin "6") (pinfunction "IN_6") (pintype "input"))
      (node (ref "IC29") (pin "7") (pinfunction "IN_7") (pintype "input"))
      (node (ref "IC29") (pin "8") (pinfunction "IN_8") (pintype "input"))
      (node (ref "IC35") (pin "15") (pinfunction "IN_15") (pintype "input"))
      (node (ref "IC35") (pin "16") (pinfunction "IN_16") (pintype "input"))
      (node (ref "IC35") (pin "17") (pinfunction "IN_17") (pintype "input"))
      (node (ref "L41") (pin "2") (pinfunction "2_2") (pintype "passive"))
    )
    (net (code "6") (name "/IN_2V5") (class "Default")
      (node (ref "C113") (pin "2") (pinfunction "2_2") (pintype "passive"))
      (node (ref "C199") (pin "2") (pinfunction "2_2") (pintype "passive"))
      (node (ref "IC33") (pin "15") (pinfunction "IN_15") (pintype "input"))
      (node (ref "IC33") (pin "16") (pinfunction "IN_16") (pintype "input"))
      (node (ref "IC33") (pin "17") (pinfunction "IN_17") (pintype "input"))
      (node (ref "IC8") (pin "5") (pinfunction "IN_5") (pintype "input"))
      (node (ref "IC8") (pin "6") (pinfunction "IN_6") (pintype "input"))
      (node (ref "IC8") (pin "7") (pinfunction "IN_7") (pintype "input"))
      (node (ref "IC8") (pin "8") (pinfunction "IN_8") (pintype "input"))
      (node (ref "L12") (pin "2") (pinfunction "2_2") (pintype "passive"))
    )
    (net (code "7") (name "/IN_3V3a") (class "Default")
      (node (ref "C118") (pin "2") (pinfunction "2_2") (pintype "passive"))
      (node (ref "C345") (pin "2") (pinfunction "2_2") (pintype "passive"))
      (node (ref "IC23") (pin "5") (pinfunction "IN_5") (pintype "input"))
      (node (ref "IC23") (pin "6") (pinfunction "IN_6") (pintype "input"))
      (node (ref "IC23") (pin "7") (pinfunction "IN_7") (pintype "input"))
      (node (ref "IC23") (pin "8") (pinfunction "IN_8") (pintype "input"))
      (node (ref "IC34") (pin "15") (pinfunction "IN_15") (pintype "input"))
      (node (ref "IC34") (pin "16") (pinfunction "IN_16") (pintype "input"))
      (node (ref "IC34") (pin "17") (pinfunction "IN_17") (pintype "input"))
      (node (ref "L40") (pin "2") (pinfunction "2_2") (pintype "passive"))
    )
    (net (code "8") (name "/IN_3V3b") (class "Default")
      (node (ref "C130") (pin "2") (pinfunction "2_2") (pintype "passive"))
      (node (ref "C369") (pin "2") (pinfunction "2_2") (pintype "passive"))
      (node (ref "IC31") (pin "5") (pinfunction "IN_5") (pintype "input"))
      (node (ref "IC31") (pin "6") (pinfunction "IN_6") (pintype "input"))
      (node (ref "IC31") (pin "7") (pinfunction "IN_7") (pintype "input"))
      (node (ref "IC31") (pin "8") (pinfunction "IN_8") (pintype "input"))
      (node (ref "IC36") (pin "15") (pinfunction "IN_15") (pintype "input"))
      (node (ref "IC36") (pin "16") (pinfunction "IN_16") (pintype "input"))
      (node (ref "IC36") (pin "17") (pinfunction "IN_17") (pintype "input"))
      (node (ref "L42") (pin "2") (pinfunction "2_2") (pintype "passive"))
    )
    (net (code "9") (name "/PG_MGTAVCC") (class "Default")
      (node (ref "IC29") (pin "9") (pinfunction "PG_9") (pintype "output"))
      (node (ref "IC35") (pin "4") (pinfunction "PG_4") (pintype "output"))
    )
    (net (code "10") (name "/PG_MGTAVTT") (class "Default")
      (node (ref "IC23") (pin "9") (pinfunction "PG_9") (pintype "output"))
      (node (ref "IC34") (pin "4") (pinfunction "PG_4") (pintype "output"))
    )
    (net (code "11") (name "/PG_MGTVCCAUX") (class "Default")
      (node (ref "IC31") (pin "9") (pinfunction "PG_9") (pintype "output"))
      (node (ref "IC36") (pin "4") (pinfunction "PG_4") (pintype "output"))
    )
    (net (code "12") (name "/PG_VCCDDR") (class "Default")
      (node (ref "IC33") (pin "4") (pinfunction "PG_4") (pintype "output"))
      (node (ref "IC8") (pin "9") (pinfunction "PG_9") (pintype "output"))
    )
    (net (code "13") (name "/VTT_DDR_PG") (class "Default")
      (node (ref "IC12") (pin "9") (pinfunction "PGOOD_9") (pintype "output"))
      (node (ref "R108") (pin "2") (pinfunction "2_2") (pintype "passive"))
      (node (ref "T6") (pin "1") (pinfunction "G_1") (pintype "passive"))
    )
    (net (code "14") (name "/V_bias") (class "Default")
      (node (ref "C376") (pin "2") (pinfunction "2_2") (pintype "passive"))
      (node (ref "C380") (pin "2") (pinfunction "2_2") (pintype "passive"))
      (node (ref "IC32") (pin "1") (pinfunction "OUT_1") (pintype "power_in"))
      (node (ref "IC38") (pin "2") (pinfunction "OUT_2") (pintype "power_in"))
      (node (ref "R117") (pin "1") (pinfunction "1_1") (pintype "passive"))
    )
    (net (code "15") (name "/Vbias") (class "Default")
      (node (ref "C361") (pin "2") (pinfunction "2_2") (pintype "passive"))
      (node (ref "C362") (pin "2") (pinfunction "2_2") (pintype "passive"))
      (node (ref "C370") (pin "2") (pinfunction "2_2") (pintype "passive"))
      (node (ref "C371") (pin "2") (pinfunction "2_2") (pintype "passive"))
      (node (ref "IC23") (pin "10") (pinfunction "BIAS_10") (pintype "input"))
      (node (ref "IC29") (pin "10") (pinfunction "BIAS_10") (pintype "input"))
      (node (ref "IC31") (pin "10") (pinfunction "BIAS_10") (pintype "input"))
      (node (ref "IC8") (pin "10") (pinfunction "BIAS_10") (pintype "input"))
      (node (ref "R117") (pin "2") (pinfunction "2_2") (pintype "passive"))
    )
    (net (code "16") (name "GND") (class "Default")
      (node (ref "C113") (pin "1") (pinfunction "1_1") (pintype "passive"))
      (node (ref "C114") (pin "1") (pinfunction "1_1") (pintype "passive"))
      (node (ref "C115") (pin "1") (pinfunction "1_1") (pintype "passive"))
      (node (ref "C116") (pin "1") (pinfunction "1_1") (pintype "passive"))
      (node (ref "C117") (pin "1") (pinfunction "1_1") (pintype "passive"))
      (node (ref "C118") (pin "1") (pinfunction "1_1") (pintype "passive"))
      (node (ref "C119") (pin "1") (pinfunction "1_1") (pintype "passive"))
      (node (ref "C120") (pin "1") (pinfunction "1_1") (pintype "passive"))
      (node (ref "C121") (pin "1") (pinfunction "1_1") (pintype "passive"))
      (node (ref "C122") (pin "1") (pinfunction "1_1") (pintype "passive"))
      (node (ref "C123") (pin "2") (pinfunction "2_2") (pintype "passive"))
      (node (ref "C124") (pin "2") (pinfunction "2_2") (pintype "passive"))
      (node (ref "C125") (pin "1") (pinfunction "1_1") (pintype "passive"))
      (node (ref "C126") (pin "1") (pinfunction "1_1") (pintype "passive"))
      (node (ref "C127") (pin "1") (pinfunction "1_1") (pintype "passive"))
      (node (ref "C128") (pin "1") (pinfunction "1_1") (pintype "passive"))
      (node (ref "C129") (pin "1") (pinfunction "1_1") (pintype "passive"))
      (node (ref "C130") (pin "1") (pinfunction "1_1") (pintype "passive"))
      (node (ref "C131") (pin "1") (pinfunction "1_1") (pintype "passive"))
      (node (ref "C132") (pin "1") (pinfunction "1_1") (pintype "passive"))
      (node (ref "C133") (pin "1") (pinfunction "1_1") (pintype "passive"))
      (node (ref "C134") (pin "1") (pinfunction "1_1") (pintype "passive"))
      (node (ref "C135") (pin "2") (pinfunction "2_2") (pintype "passive"))
      (node (ref "C136") (pin "2") (pinfunction "2_2") (pintype "passive"))
      (node (ref "C199") (pin "1") (pinfunction "1_1") (pintype "passive"))
      (node (ref "C325") (pin "2") (pinfunction "2_2") (pintype "passive"))
      (node (ref "C326") (pin "2") (pinfunction "2_2") (pintype "passive"))
      (node (ref "C327") (pin "2") (pinfunction "2_2") (pintype "passive"))
      (node (ref "C328") (pin "1") (pinfunction "1_1") (pintype "passive"))
      (node (ref "C329") (pin "1") (pinfunction "1_1") (pintype "passive"))
      (node (ref "C345") (pin "1") (pinfunction "1_1") (pintype "passive"))
      (node (ref "C361") (pin "1") (pinfunction "1_1") (pintype "passive"))
      (node (ref "C362") (pin "1") (pinfunction "1_1") (pintype "passive"))
      (node (ref "C366") (pin "2") (pinfunction "2_2") (pintype "passive"))
      (node (ref "C367") (pin "2") (pinfunction "2_2") (pintype "passive"))
      (node (ref "C368") (pin "1") (pinfunction "1_1") (pintype "passive"))
      (node (ref "C369") (pin "1") (pinfunction "1_1") (pintype "passive"))
      (node (ref "C370") (pin "1") (pinfunction "1_1") (pintype "passive"))
      (node (ref "C371") (pin "1") (pinfunction "1_1") (pintype "passive"))
      (node (ref "C372") (pin "2") (pinfunction "2_2") (pintype "passive"))
      (node (ref "C373") (pin "2") (pinfunction "2_2") (pintype "passive"))
      (node (ref "C374") (pin "1") (pinfunction "1_1") (pintype "passive"))
      (node (ref "C375") (pin "1") (pinfunction "1_1") (pintype "passive"))
      (node (ref "C376") (pin "1") (pinfunction "1_1") (pintype "passive"))
      (node (ref "C380") (pin "1") (pinfunction "1_1") (pintype "passive"))
      (node (ref "C51") (pin "2") (pinfunction "2_2") (pintype "passive"))
      (node (ref "IC12") (pin "11") (pinfunction "EP_11") (pintype "power_in"))
      (node (ref "IC12") (pin "4") (pinfunction "PGND_4") (pintype "power_in"))
      (node (ref "IC12") (pin "8") (pinfunction "GND_8") (pintype "power_in"))
      (node (ref "IC23") (pin "12") (pinfunction "GND_12") (pintype "power_in"))
      (node (ref "IC23") (pin "21") (pinfunction "GND_21") (pintype "power_in"))
      (node (ref "IC29") (pin "12") (pinfunction "GND_12") (pintype "power_in"))
      (node (ref "IC29") (pin "21") (pinfunction "GND_21") (pintype "power_in"))
      (node (ref "IC31") (pin "12") (pinfunction "GND_12") (pintype "power_in"))
      (node (ref "IC31") (pin "21") (pinfunction "GND_21") (pintype "power_in"))
      (node (ref "IC32") (pin "3") (pinfunction "GND_3") (pintype "power_in"))
      (node (ref "IC33") (pin "18") (pinfunction "GND_18") (pintype "power_in"))
      (node (ref "IC33") (pin "21") (pinfunction "EP_21") (pintype "power_in"))
      (node (ref "IC33") (pin "8") (pinfunction "GND_8") (pintype "power_in"))
      (node (ref "IC34") (pin "18") (pinfunction "GND_18") (pintype "power_in"))
      (node (ref "IC34") (pin "21") (pinfunction "EP_21") (pintype "power_in"))
      (node (ref "IC34") (pin "8") (pinfunction "GND_8") (pintype "power_in"))
      (node (ref "IC35") (pin "18") (pinfunction "GND_18") (pintype "power_in"))
      (node (ref "IC35") (pin "21") (pinfunction "EP_21") (pintype "power_in"))
      (node (ref "IC35") (pin "8") (pinfunction "GND_8") (pintype "power_in"))
      (node (ref "IC36") (pin "18") (pinfunction "GND_18") (pintype "power_in"))
      (node (ref "IC36") (pin "21") (pinfunction "EP_21") (pintype "power_in"))
      (node (ref "IC36") (pin "8") (pinfunction "GND_8") (pintype "power_in"))
      (node (ref "IC38") (pin "3") (pinfunction "GND_3") (pintype "power_in"))
      (node (ref "IC8") (pin "12") (pinfunction "GND_12") (pintype "power_in"))
      (node (ref "IC8") (pin "21") (pinfunction "GND_21") (pintype "power_in"))
      (node (ref "R104") (pin "1") (pinfunction "1_1") (pintype "passive"))
      (node (ref "R105") (pin "1") (pinfunction "1_1") (pintype "passive"))
      (node (ref "R110") (pin "1") (pinfunction "1_1") (pintype "passive"))
      (node (ref "R113") (pin "1") (pinfunction "1_1") (pintype "passive"))
      (node (ref "R363") (pin "2") (pinfunction "2_2") (pintype "passive"))
      (node (ref "R63") (pin "1") (pinfunction "1_1") (pintype "passive"))
      (node (ref "R95") (pin "1") (pinfunction "1_1") (pintype "passive"))
      (node (ref "R96") (pin "1") (pinfunction "1_1") (pintype "passive"))
      (node (ref "R99") (pin "1") (pinfunction "1_1") (pintype "passive"))
      (node (ref "T6") (pin "2") (pinfunction "S_2") (pintype "passive"))
    )
    (net (code "17") (name "MGTAVCC") (class "Default")
      (node (ref "C126") (pin "2") (pinfunction "2_2") (pintype "passive"))
      (node (ref "C127") (pin "2") (pinfunction "2_2") (pintype "passive"))
      (node (ref "C159") (pin "2") (pinfunction "2_2") (pintype "passive"))
      (node (ref "IC29") (pin "1") (pinfunction "OUT_1") (pintype "power_in"))
      (node (ref "IC29") (pin "18") (pinfunction "OUT_18") (pintype "power_in"))
      (node (ref "IC29") (pin "19") (pinfunction "OUT_19") (pintype "power_in"))
      (node (ref "IC29") (pin "20") (pinfunction "OUT_20") (pintype "power_in"))
      (node (ref "IC35") (pin "1") (pinfunction "OUT_1") (pintype "output"))
      (node (ref "IC35") (pin "19") (pinfunction "OUT_19") (pintype "output"))
      (node (ref "IC35") (pin "20") (pinfunction "OUT_20") (pintype "output"))
      (node (ref "L7") (pin "1") (pinfunction "1_1") (pintype "passive"))
      (node (ref "R100") (pin "2") (pinfunction "2_2") (pintype "passive"))
      (node (ref "R101") (pin "2") (pinfunction "2_2") (pintype "passive"))
    )
    (net (code "18") (name "MGTAVTT") (class "Default")
      (node (ref "C119") (pin "2") (pinfunction "2_2") (pintype "passive"))
      (node (ref "C120") (pin "2") (pinfunction "2_2") (pintype "passive"))
      (node (ref "C157") (pin "2") (pinfunction "2_2") (pintype "passive"))
      (node (ref "IC23") (pin "1") (pinfunction "OUT_1") (pintype "power_in"))
      (node (ref "IC23") (pin "18") (pinfunction "OUT_18") (pintype "power_in"))
      (node (ref "IC23") (pin "19") (pinfunction "OUT_19") (pintype "power_in"))
      (node (ref "IC23") (pin "20") (pinfunction "OUT_20") (pintype "power_in"))
      (node (ref "IC34") (pin "1") (pinfunction "OUT_1") (pintype "output"))
      (node (ref "IC34") (pin "19") (pinfunction "OUT_19") (pintype "output"))
      (node (ref "IC34") (pin "20") (pinfunction "OUT_20") (pintype "output"))
      (node (ref "L5") (pin "1") (pinfunction "1_1") (pintype "passive"))
      (node (ref "R62") (pin "2") (pinfunction "2_2") (pintype "passive"))
      (node (ref "R94") (pin "2") (pinfunction "2_2") (pintype "passive"))
    )
    (net (code "19") (name "MGTVCCAUX") (class "Default")
      (node (ref "C131") (pin "2") (pinfunction "2_2") (pintype "passive"))
      (node (ref "C132") (pin "2") (pinfunction "2_2") (pintype "passive"))
      (node (ref "C158") (pin "2") (pinfunction "2_2") (pintype "passive"))
      (node (ref "IC31") (pin "1") (pinfunction "OUT_1") (pintype "power_in"))
      (node (ref "IC31") (pin "18") (pinfunction "OUT_18") (pintype "power_in"))
      (node (ref "IC31") (pin "19") (pinfunction "OUT_19") (pintype "power_in"))
      (node (ref "IC31") (pin "20") (pinfunction "OUT_20") (pintype "power_in"))
      (node (ref "IC36") (pin "1") (pinfunction "OUT_1") (pintype "output"))
      (node (ref "IC36") (pin "19") (pinfunction "OUT_19") (pintype "output"))
      (node (ref "IC36") (pin "20") (pinfunction "OUT_20") (pintype "output"))
      (node (ref "L8") (pin "1") (pinfunction "1_1") (pintype "passive"))
      (node (ref "R102") (pin "2") (pinfunction "2_2") (pintype "passive"))
      (node (ref "R103") (pin "2") (pinfunction "2_2") (pintype "passive"))
    )
    (net (code "20") (name "MGT_AVCC") (class "Default")
      (node (ref "C128") (pin "2") (pinfunction "2_2") (pintype "passive"))
      (node (ref "C129") (pin "2") (pinfunction "2_2") (pintype "passive"))
      (node (ref "L7") (pin "2") (pinfunction "2_2") (pintype "passive"))
      (node (ref "TP51") (pin "1") (pinfunction "1_1") (pintype "bidirectional"))
    )
    (net (code "21") (name "MGT_AVTT") (class "Default")
      (node (ref "B2") (pin "1") (pinfunction "1_1") (pintype "bidirectional"))
      (node (ref "C121") (pin "2") (pinfunction "2_2") (pintype "passive"))
      (node (ref "C122") (pin "2") (pinfunction "2_2") (pintype "passive"))
      (node (ref "L5") (pin "2") (pinfunction "2_2") (pintype "passive"))
    )
    (net (code "22") (name "MGT_VCCAUX") (class "Default")
      (node (ref "C133") (pin "2") (pinfunction "2_2") (pintype "passive"))
      (node (ref "C134") (pin "2") (pinfunction "2_2") (pintype "passive"))
      (node (ref "L8") (pin "2") (pinfunction "2_2") (pintype "passive"))
      (node (ref "TP41") (pin "1") (pinfunction "1_1") (pintype "bidirectional"))
    )
    (net (code "23") (name "Net-(IC8-FB)") (class "Default")
      (node (ref "IC8") (pin "16") (pinfunction "FB_16") (pintype "input"))
      (node (ref "R59") (pin "1") (pinfunction "1_1") (pintype "passive"))
      (node (ref "R63") (pin "2") (pinfunction "2_2") (pintype "passive"))
    )
    (net (code "24") (name "Net-(IC8-SS)") (class "Default")
      (node (ref "C366") (pin "1") (pinfunction "1_1") (pintype "passive"))
      (node (ref "IC8") (pin "15") (pinfunction "SS_15") (pintype "output"))
    )
    (net (code "25") (name "Net-(IC12-REFIN)") (class "Default")
      (node (ref "C328") (pin "2") (pinfunction "2_2") (pintype "passive"))
      (node (ref "IC12") (pin "1") (pinfunction "REFIN_1") (pintype "input"))
      (node (ref "R362") (pin "2") (pinfunction "2_2") (pintype "passive"))
      (node (ref "R363") (pin "1") (pinfunction "1_1") (pintype "passive"))
    )
    (net (code "26") (name "Net-(IC23-FB)") (class "Default")
      (node (ref "IC23") (pin "16") (pinfunction "FB_16") (pintype "input"))
      (node (ref "R62") (pin "1") (pinfunction "1_1") (pintype "passive"))
      (node (ref "R95") (pin "2") (pinfunction "2_2") (pintype "passive"))
    )
    (net (code "27") (name "Net-(IC23-SS)") (class "Default")
      (node (ref "C367") (pin "1") (pinfunction "1_1") (pintype "passive"))
      (node (ref "IC23") (pin "15") (pinfunction "SS_15") (pintype "output"))
    )
    (net (code "28") (name "Net-(IC29-FB)") (class "Default")
      (node (ref "IC29") (pin "16") (pinfunction "FB_16") (pintype "input"))
      (node (ref "R100") (pin "1") (pinfunction "1_1") (pintype "passive"))
      (node (ref "R110") (pin "2") (pinfunction "2_2") (pintype "passive"))
    )
    (net (code "29") (name "Net-(IC29-SS)") (class "Default")
      (node (ref "C372") (pin "1") (pinfunction "1_1") (pintype "passive"))
      (node (ref "IC29") (pin "15") (pinfunction "SS_15") (pintype "output"))
    )
    (net (code "30") (name "Net-(IC31-FB)") (class "Default")
      (node (ref "IC31") (pin "16") (pinfunction "FB_16") (pintype "input"))
      (node (ref "R102") (pin "1") (pinfunction "1_1") (pintype "passive"))
      (node (ref "R113") (pin "2") (pinfunction "2_2") (pintype "passive"))
    )
    (net (code "31") (name "Net-(IC31-SS)") (class "Default")
      (node (ref "C373") (pin "1") (pinfunction "1_1") (pintype "passive"))
      (node (ref "IC31") (pin "15") (pinfunction "SS_15") (pintype "output"))
    )
    (net (code "32") (name "Net-(IC32-IN)") (class "Default")
      (node (ref "C375") (pin "2") (pinfunction "2_2") (pintype "passive"))
      (node (ref "IC32") (pin "2") (pinfunction "IN_2") (pintype "input"))
      (node (ref "IC38") (pin "1") (pinfunction "IN_1") (pintype "input"))
      (node (ref "L27") (pin "2") (pinfunction "2_2") (pintype "passive"))
    )
    (net (code "33") (name "Net-(IC33-FB)") (class "Default")
      (node (ref "C76") (pin "1") (pinfunction "1_1") (pintype "passive"))
      (node (ref "IC33") (pin "3") (pinfunction "FB_3") (pintype "input"))
      (node (ref "R92") (pin "1") (pinfunction "1_1") (pintype "passive"))
      (node (ref "R96") (pin "2") (pinfunction "2_2") (pintype "passive"))
    )
    (net (code "34") (name "Net-(IC33-SS)") (class "Default")
      (node (ref "C123") (pin "1") (pinfunction "1_1") (pintype "passive"))
      (node (ref "IC33") (pin "13") (pinfunction "SS_13") (pintype "passive"))
    )
    (net (code "35") (name "Net-(IC34-FB)") (class "Default")
      (node (ref "C157") (pin "1") (pinfunction "1_1") (pintype "passive"))
      (node (ref "IC34") (pin "3") (pinfunction "FB_3") (pintype "input"))
      (node (ref "R94") (pin "1") (pinfunction "1_1") (pintype "passive"))
      (node (ref "R99") (pin "2") (pinfunction "2_2") (pintype "passive"))
    )
    (net (code "36") (name "Net-(IC34-SS)") (class "Default")
      (node (ref "C124") (pin "1") (pinfunction "1_1") (pintype "passive"))
      (node (ref "IC34") (pin "13") (pinfunction "SS_13") (pintype "passive"))
    )
    (net (code "37") (name "Net-(IC35-FB)") (class "Default")
      (node (ref "C159") (pin "1") (pinfunction "1_1") (pintype "passive"))
      (node (ref "IC35") (pin "3") (pinfunction "FB_3") (pintype "input"))
      (node (ref "R101") (pin "1") (pinfunction "1_1") (pintype "passive"))
      (node (ref "R104") (pin "2") (pinfunction "2_2") (pintype "passive"))
    )
    (net (code "38") (name "Net-(IC35-SS)") (class "Default")
      (node (ref "C135") (pin "1") (pinfunction "1_1") (pintype "passive"))
      (node (ref "IC35") (pin "13") (pinfunction "SS_13") (pintype "passive"))
    )
    (net (code "39") (name "Net-(IC36-FB)") (class "Default")
      (node (ref "C158") (pin "1") (pinfunction "1_1") (pintype "passive"))
      (node (ref "IC36") (pin "3") (pinfunction "FB_3") (pintype "input"))
      (node (ref "R103") (pin "1") (pinfunction "1_1") (pintype "passive"))
      (node (ref "R105") (pin "2") (pinfunction "2_2") (pintype "passive"))
    )
    (net (code "40") (name "Net-(IC36-SS)") (class "Default")
      (node (ref "C136") (pin "1") (pinfunction "1_1") (pintype "passive"))
      (node (ref "IC36") (pin "13") (pinfunction "SS_13") (pintype "passive"))
    )
    (net (code "41") (name "Net-(LD4-A)") (class "Default")
      (node (ref "LD4") (pin "2") (pinfunction "A_2") (pintype "passive"))
      (node (ref "R364") (pin "1") (pinfunction "1_1") (pintype "passive"))
    )
    (net (code "42") (name "Net-(LD4-C)") (class "Default")
      (node (ref "LD4") (pin "1") (pinfunction "C_1") (pintype "passive"))
      (node (ref "T6") (pin "3") (pinfunction "D_3") (pintype "passive"))
    )
    (net (code "43") (name "P1V8") (class "Default")
      (node (ref "L41") (pin "1") (pinfunction "1_1") (pintype "passive"))
    )
    (net (code "44") (name "P2V5") (class "Default")
      (node (ref "L12") (pin "1") (pinfunction "1_1") (pintype "passive"))
    )
    (net (code "45") (name "P3V3") (class "Default")
      (node (ref "C51") (pin "1") (pinfunction "1_1") (pintype "passive"))
      (node (ref "IC12") (pin "10") (pinfunction "VIN_10") (pintype "input"))
      (node (ref "IC12") (pin "7") (pinfunction "EN_7") (pintype "input"))
      (node (ref "L40") (pin "1") (pinfunction "1_1") (pintype "passive"))
      (node (ref "L42") (pin "1") (pinfunction "1_1") (pintype "passive"))
      (node (ref "R108") (pin "1") (pinfunction "1_1") (pintype "passive"))
      (node (ref "R364") (pin "2") (pinfunction "2_2") (pintype "passive"))
    )
    (net (code "46") (name "P12V0_FLT") (class "Default")
      (node (ref "C374") (pin "2") (pinfunction "2_2") (pintype "passive"))
      (node (ref "L27") (pin "1") (pinfunction "1_1") (pintype "passive"))
    )
    (net (code "47") (name "VCCDDR") (class "Default")
      (node (ref "C116") (pin "2") (pinfunction "2_2") (pintype "passive"))
      (node (ref "C117") (pin "2") (pinfunction "2_2") (pintype "passive"))
      (node (ref "C327") (pin "1") (pinfunction "1_1") (pintype "passive"))
      (node (ref "IC12") (pin "2") (pinfunction "VLDOIN_2") (pintype "input"))
      (node (ref "L6") (pin "2") (pinfunction "2_2") (pintype "passive"))
      (node (ref "R362") (pin "1") (pinfunction "1_1") (pintype "passive"))
    )
    (net (code "48") (name "VCC_DDR") (class "Default")
      (node (ref "C114") (pin "2") (pinfunction "2_2") (pintype "passive"))
      (node (ref "C115") (pin "2") (pinfunction "2_2") (pintype "passive"))
      (node (ref "C76") (pin "2") (pinfunction "2_2") (pintype "passive"))
      (node (ref "IC33") (pin "1") (pinfunction "OUT_1") (pintype "output"))
      (node (ref "IC33") (pin "19") (pinfunction "OUT_19") (pintype "output"))
      (node (ref "IC33") (pin "20") (pinfunction "OUT_20") (pintype "output"))
      (node (ref "IC8") (pin "1") (pinfunction "OUT_1") (pintype "power_in"))
      (node (ref "IC8") (pin "18") (pinfunction "OUT_18") (pintype "power_in"))
      (node (ref "IC8") (pin "19") (pinfunction "OUT_19") (pintype "power_in"))
      (node (ref "IC8") (pin "20") (pinfunction "OUT_20") (pintype "power_in"))
      (node (ref "L6") (pin "1") (pinfunction "1_1") (pintype "passive"))
      (node (ref "R59") (pin "2") (pinfunction "2_2") (pintype "passive"))
      (node (ref "R92") (pin "2") (pinfunction "2_2") (pintype "passive"))
    )
    (net (code "49") (name "VREF_DDR") (class "Default")
      (node (ref "C329") (pin "2") (pinfunction "2_2") (pintype "passive"))
      (node (ref "IC12") (pin "6") (pinfunction "REFOUT_6") (pintype "output"))
    )
    (net (code "50") (name "VTT_DDR") (class "Default")
      (node (ref "C325") (pin "1") (pinfunction "1_1") (pintype "passive"))
      (node (ref "C326") (pin "1") (pinfunction "1_1") (pintype "passive"))
      (node (ref "IC12") (pin "3") (pinfunction "VO_3") (pintype "power_in"))
      (node (ref "IC12") (pin "5") (pinfunction "VOSNS_5") (pintype "input"))
      (node (ref "TP52") (pin "1") (pinfunction "1_1") (pintype "bidirectional"))
    )
    (net (code "51") (name "unconnected-(IC8-NC-Pad2)") (class "Default")
      (node (ref "IC8") (pin "2") (pinfunction "NC_2") (pintype "passive"))
    )
    (net (code "52") (name "unconnected-(IC8-NC-Pad3)") (class "Default")
      (node (ref "IC8") (pin "3") (pinfunction "NC_3") (pintype "passive"))
    )
    (net (code "53") (name "unconnected-(IC8-NC-Pad4)") (class "Default")
      (node (ref "IC8") (pin "4") (pinfunction "NC_4") (pintype "passive"))
    )
    (net (code "54") (name "unconnected-(IC8-NC-Pad13)") (class "Default")
      (node (ref "IC8") (pin "13") (pinfunction "NC_13") (pintype "passive"))
    )
    (net (code "55") (name "unconnected-(IC8-NC-Pad14)") (class "Default")
      (node (ref "IC8") (pin "14") (pinfunction "NC_14") (pintype "passive"))
    )
    (net (code "56") (name "unconnected-(IC8-NC-Pad17)") (class "Default")
      (node (ref "IC8") (pin "17") (pinfunction "NC_17") (pintype "passive"))
    )
    (net (code "57") (name "unconnected-(IC23-NC-Pad2)") (class "Default")
      (node (ref "IC23") (pin "2") (pinfunction "NC_2") (pintype "passive"))
    )
    (net (code "58") (name "unconnected-(IC23-NC-Pad3)") (class "Default")
      (node (ref "IC23") (pin "3") (pinfunction "NC_3") (pintype "passive"))
    )
    (net (code "59") (name "unconnected-(IC23-NC-Pad4)") (class "Default")
      (node (ref "IC23") (pin "4") (pinfunction "NC_4") (pintype "passive"))
    )
    (net (code "60") (name "unconnected-(IC23-NC-Pad13)") (class "Default")
      (node (ref "IC23") (pin "13") (pinfunction "NC_13") (pintype "passive"))
    )
    (net (code "61") (name "unconnected-(IC23-NC-Pad14)") (class "Default")
      (node (ref "IC23") (pin "14") (pinfunction "NC_14") (pintype "passive"))
    )
    (net (code "62") (name "unconnected-(IC23-NC-Pad17)") (class "Default")
      (node (ref "IC23") (pin "17") (pinfunction "NC_17") (pintype "passive"))
    )
    (net (code "63") (name "unconnected-(IC29-NC-Pad2)") (class "Default")
      (node (ref "IC29") (pin "2") (pinfunction "NC_2") (pintype "passive"))
    )
    (net (code "64") (name "unconnected-(IC29-NC-Pad3)") (class "Default")
      (node (ref "IC29") (pin "3") (pinfunction "NC_3") (pintype "passive"))
    )
    (net (code "65") (name "unconnected-(IC29-NC-Pad4)") (class "Default")
      (node (ref "IC29") (pin "4") (pinfunction "NC_4") (pintype "passive"))
    )
    (net (code "66") (name "unconnected-(IC29-NC-Pad13)") (class "Default")
      (node (ref "IC29") (pin "13") (pinfunction "NC_13") (pintype "passive"))
    )
    (net (code "67") (name "unconnected-(IC29-NC-Pad14)") (class "Default")
      (node (ref "IC29") (pin "14") (pinfunction "NC_14") (pintype "passive"))
    )
    (net (code "68") (name "unconnected-(IC29-NC-Pad17)") (class "Default")
      (node (ref "IC29") (pin "17") (pinfunction "NC_17") (pintype "passive"))
    )
    (net (code "69") (name "unconnected-(IC31-NC-Pad2)") (class "Default")
      (node (ref "IC31") (pin "2") (pinfunction "NC_2") (pintype "passive"))
    )
    (net (code "70") (name "unconnected-(IC31-NC-Pad3)") (class "Default")
      (node (ref "IC31") (pin "3") (pinfunction "NC_3") (pintype "passive"))
    )
    (net (code "71") (name "unconnected-(IC31-NC-Pad4)") (class "Default")
      (node (ref "IC31") (pin "4") (pinfunction "NC_4") (pintype "passive"))
    )
    (net (code "72") (name "unconnected-(IC31-NC-Pad13)") (class "Default")
      (node (ref "IC31") (pin "13") (pinfunction "NC_13") (pintype "passive"))
    )
    (net (code "73") (name "unconnected-(IC31-NC-Pad14)") (class "Default")
      (node (ref "IC31") (pin "14") (pinfunction "NC_14") (pintype "passive"))
    )
    (net (code "74") (name "unconnected-(IC31-NC-Pad17)") (class "Default")
      (node (ref "IC31") (pin "17") (pinfunction "NC_17") (pintype "passive"))
    )
    (net (code "75") (name "unconnected-(IC33-1.6V-Pad11)") (class "Default")
      (node (ref "IC33") (pin "11") (pinfunction "1.6V_11") (pintype "input+no_connect"))
    )
    (net (code "76") (name "unconnected-(IC33-50mV-Pad5)") (class "Default")
      (node (ref "IC33") (pin "5") (pinfunction "50mV_5") (pintype "input+no_connect"))
    )
    (net (code "77") (name "unconnected-(IC33-100mV-Pad6)") (class "Default")
      (node (ref "IC33") (pin "6") (pinfunction "100mV_6") (pintype "input+no_connect"))
    )
    (net (code "78") (name "unconnected-(IC33-200mV-Pad7)") (class "Default")
      (node (ref "IC33") (pin "7") (pinfunction "200mV_7") (pintype "input+no_connect"))
    )
    (net (code "79") (name "unconnected-(IC33-400mV-Pad9)") (class "Default")
      (node (ref "IC33") (pin "9") (pinfunction "400mV_9") (pintype "input+no_connect"))
    )
    (net (code "80") (name "unconnected-(IC33-800mV-Pad10)") (class "Default")
      (node (ref "IC33") (pin "10") (pinfunction "800mV_10") (pintype "input+no_connect"))
    )
    (net (code "81") (name "unconnected-(IC33-NC-Pad12)") (class "Default")
      (node (ref "IC33") (pin "12") (pinfunction "NC_12") (pintype "passive"))
    )
    (net (code "82") (name "unconnected-(IC33-SNS-Pad2)") (class "Default")
      (node (ref "IC33") (pin "2") (pinfunction "SNS_2") (pintype "input+no_connect"))
    )
    (net (code "83") (name "unconnected-(IC34-1.6V-Pad11)") (class "Default")
      (node (ref "IC34") (pin "11") (pinfunction "1.6V_11") (pintype "input+no_connect"))
    )
    (net (code "84") (name "unconnected-(IC34-50mV-Pad5)") (class "Default")
      (node (ref "IC34") (pin "5") (pinfunction "50mV_5") (pintype "input+no_connect"))
    )
    (net (code "85") (name "unconnected-(IC34-100mV-Pad6)") (class "Default")
      (node (ref "IC34") (pin "6") (pinfunction "100mV_6") (pintype "input+no_connect"))
    )
    (net (code "86") (name "unconnected-(IC34-200mV-Pad7)") (class "Default")
      (node (ref "IC34") (pin "7") (pinfunction "200mV_7") (pintype "input+no_connect"))
    )
    (net (code "87") (name "unconnected-(IC34-400mV-Pad9)") (class "Default")
      (node (ref "IC34") (pin "9") (pinfunction "400mV_9") (pintype "input+no_connect"))
    )
    (net (code "88") (name "unconnected-(IC34-800mV-Pad10)") (class "Default")
      (node (ref "IC34") (pin "10") (pinfunction "800mV_10") (pintype "input+no_connect"))
    )
    (net (code "89") (name "unconnected-(IC34-NC-Pad12)") (class "Default")
      (node (ref "IC34") (pin "12") (pinfunction "NC_12") (pintype "passive"))
    )
    (net (code "90") (name "unconnected-(IC34-SNS-Pad2)") (class "Default")
      (node (ref "IC34") (pin "2") (pinfunction "SNS_2") (pintype "input+no_connect"))
    )
    (net (code "91") (name "unconnected-(IC35-1.6V-Pad11)") (class "Default")
      (node (ref "IC35") (pin "11") (pinfunction "1.6V_11") (pintype "input+no_connect"))
    )
    (net (code "92") (name "unconnected-(IC35-50mV-Pad5)") (class "Default")
      (node (ref "IC35") (pin "5") (pinfunction "50mV_5") (pintype "input+no_connect"))
    )
    (net (code "93") (name "unconnected-(IC35-100mV-Pad6)") (class "Default")
      (node (ref "IC35") (pin "6") (pinfunction "100mV_6") (pintype "input+no_connect"))
    )
    (net (code "94") (name "unconnected-(IC35-200mV-Pad7)") (class "Default")
      (node (ref "IC35") (pin "7") (pinfunction "200mV_7") (pintype "input+no_connect"))
    )
    (net (code "95") (name "unconnected-(IC35-400mV-Pad9)") (class "Default")
      (node (ref "IC35") (pin "9") (pinfunction "400mV_9") (pintype "input+no_connect"))
    )
    (net (code "96") (name "unconnected-(IC35-800mV-Pad10)") (class "Default")
      (node (ref "IC35") (pin "10") (pinfunction "800mV_10") (pintype "input+no_connect"))
    )
    (net (code "97") (name "unconnected-(IC35-NC-Pad12)") (class "Default")
      (node (ref "IC35") (pin "12") (pinfunction "NC_12") (pintype "passive"))
    )
    (net (code "98") (name "unconnected-(IC35-SNS-Pad2)") (class "Default")
      (node (ref "IC35") (pin "2") (pinfunction "SNS_2") (pintype "input+no_connect"))
    )
    (net (code "99") (name "unconnected-(IC36-1.6V-Pad11)") (class "Default")
      (node (ref "IC36") (pin "11") (pinfunction "1.6V_11") (pintype "input+no_connect"))
    )
    (net (code "100") (name "unconnected-(IC36-50mV-Pad5)") (class "Default")
      (node (ref "IC36") (pin "5") (pinfunction "50mV_5") (pintype "input+no_connect"))
    )
    (net (code "101") (name "unconnected-(IC36-100mV-Pad6)") (class "Default")
      (node (ref "IC36") (pin "6") (pinfunction "100mV_6") (pintype "input+no_connect"))
    )
    (net (code "102") (name "unconnected-(IC36-200mV-Pad7)") (class "Default")
      (node (ref "IC36") (pin "7") (pinfunction "200mV_7") (pintype "input+no_connect"))
    )
    (net (code "103") (name "unconnected-(IC36-400mV-Pad9)") (class "Default")
      (node (ref "IC36") (pin "9") (pinfunction "400mV_9") (pintype "input+no_connect"))
    )
    (net (code "104") (name "unconnected-(IC36-800mV-Pad10)") (class "Default")
      (node (ref "IC36") (pin "10") (pinfunction "800mV_10") (pintype "input+no_connect"))
    )
    (net (code "105") (name "unconnected-(IC36-NC-Pad12)") (class "Default")
      (node (ref "IC36") (pin "12") (pinfunction "NC_12") (pintype "passive"))
    )
    (net (code "106") (name "unconnected-(IC36-SNS-Pad2)") (class "Default")
      (node (ref "IC36") (pin "2") (pinfunction "SNS_2") (pintype "input+no_connect"))
    )
  )
)
